# MainBoard.net
KiCad netlist of a schematic drawn in EAGLE
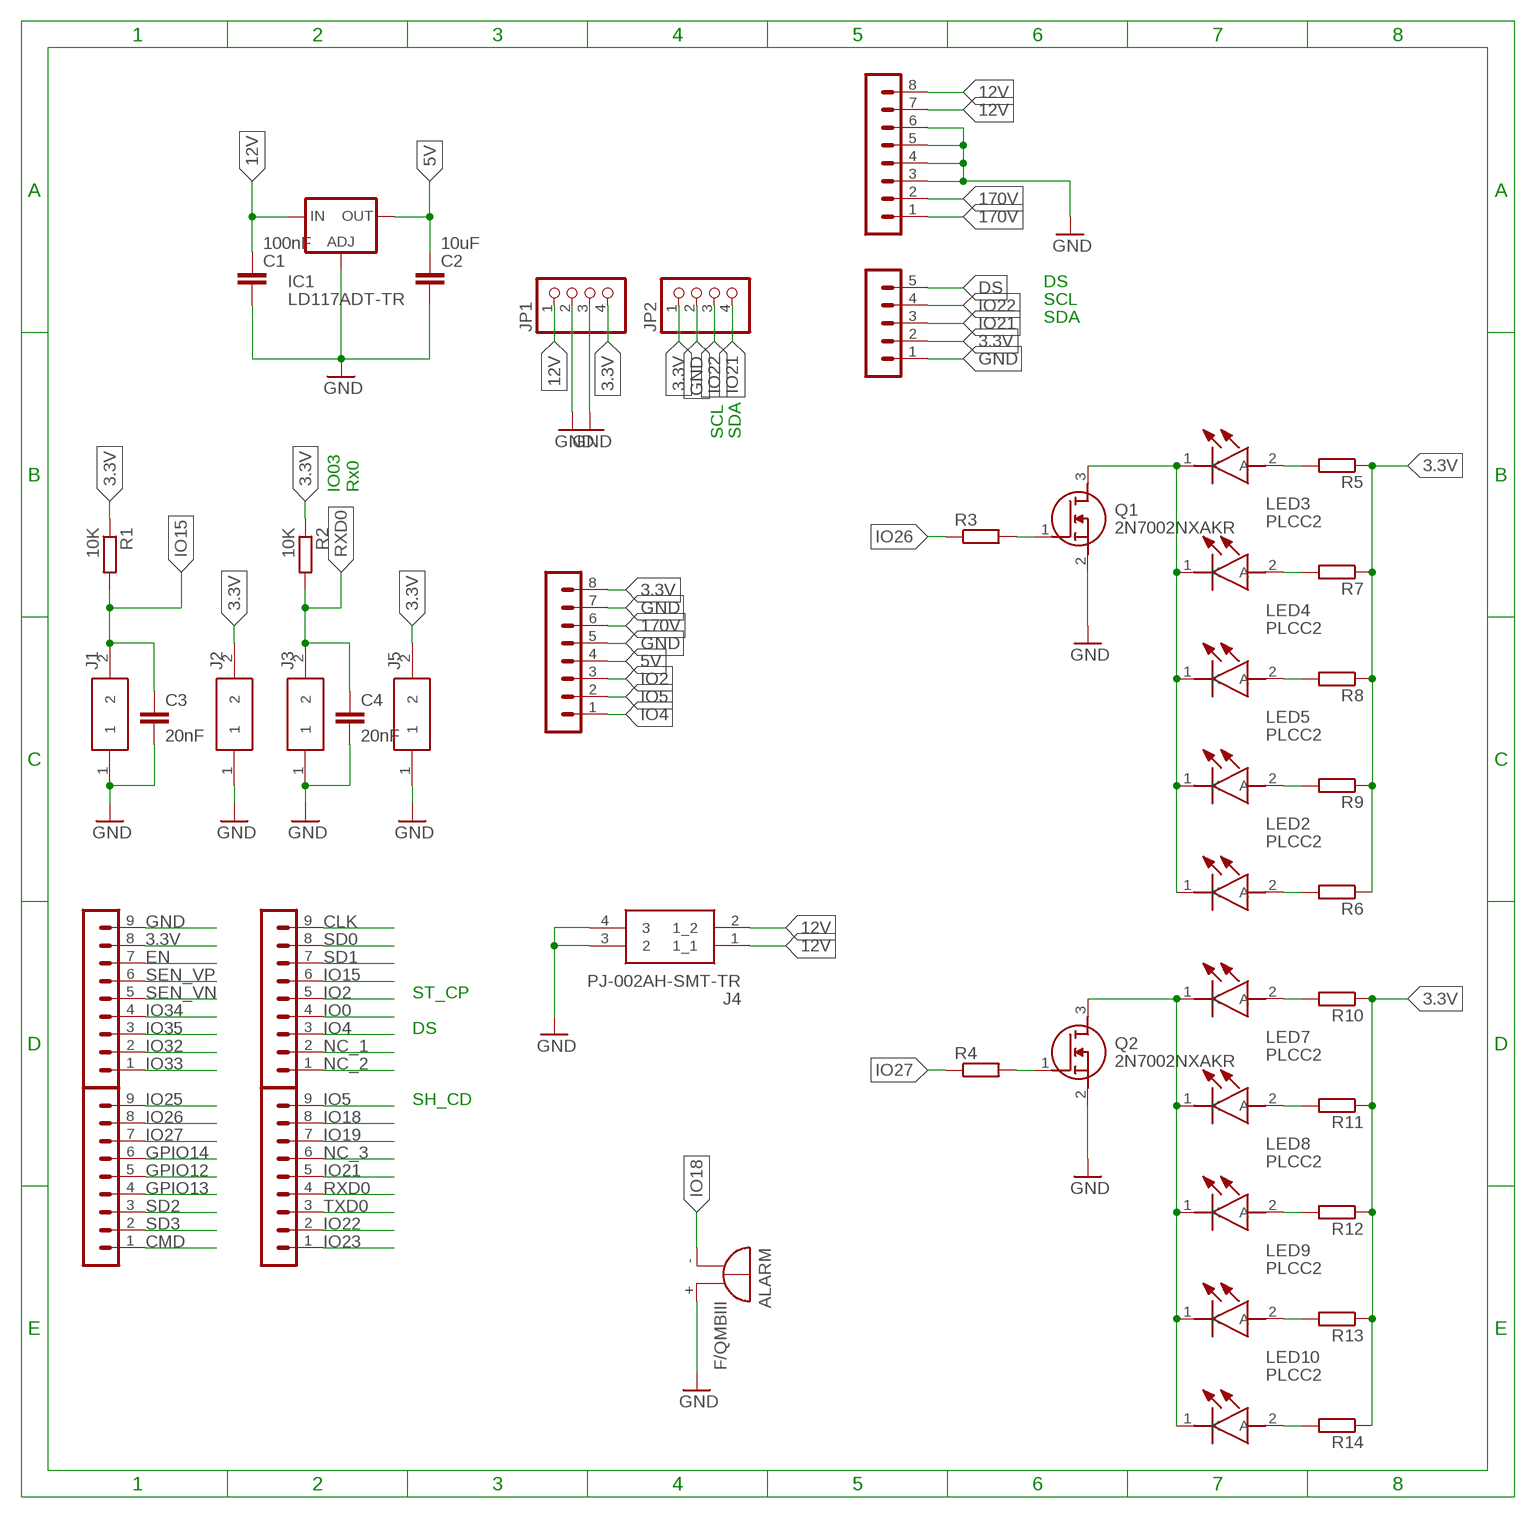
[diagram p0: schematic, sheet 1]

(export (version "E")
  (design (tool "Eeschema 10.0.6"))
  (components
    (comp (ref "ALARM")
      (value "F/QMBIII")
      (footprint "eagle-import:F_QMBIII")
      (libsource (lib "eagle-import") (part "F/QMBIII"))
    )
    (comp (ref "C1")
      (value "100nF")
      (footprint "eagle-import:C1206")
      (libsource (lib "eagle-import") (part "C-EU_1206C1206"))
    )
    (comp (ref "C2")
      (value "10uF")
      (footprint "eagle-import:C1206")
      (libsource (lib "eagle-import") (part "C-EU_1206C1206"))
    )
    (comp (ref "C3")
      (value "20nF")
      (footprint "eagle-import:C0805")
      (libsource (lib "eagle-import") (part "C-EU_805C0805"))
    )
    (comp (ref "C4")
      (value "20nF")
      (footprint "eagle-import:C0805")
      (libsource (lib "eagle-import") (part "C-EU_805C0805"))
    )
    (comp (ref "IC1")
      (value "LD117ADT-TR")
      (footprint "eagle-import:DPACK")
      (libsource (lib "eagle-import") (part "LD117A?DT-TR"))
    )
    (comp (ref "J1")
      (value "S2B-NSHSS-TB")
      (footprint "eagle-import:SM02B-NSHSS-TB")
      (fields (field (name "MANUFACTURER_PART_NUMBER") "SM02B-NSHSS-TB(LF)(SN)"))
      (libsource (lib "eagle-import") (part "S2B-NSHSS-TB"))
    )
    (comp (ref "J2")
      (value "S2B-NSHSS-TB")
      (footprint "eagle-import:SM02B-NSHSS-TB")
      (fields (field (name "MANUFACTURER_PART_NUMBER") "SM02B-NSHSS-TB(LF)(SN)"))
      (libsource (lib "eagle-import") (part "S2B-NSHSS-TB"))
    )
    (comp (ref "J3")
      (value "S2B-NSHSS-TB")
      (footprint "eagle-import:SM02B-NSHSS-TB")
      (fields (field (name "MANUFACTURER_PART_NUMBER") "SM02B-NSHSS-TB(LF)(SN)"))
      (libsource (lib "eagle-import") (part "S2B-NSHSS-TB"))
    )
    (comp (ref "J4")
      (value "PJ-002AH-SMT-TR")
      (footprint "eagle-import:PJ-002AH-SMT-TR")
      (fields (field (name "MOUSER_PART_NUMBER") "490-PJ-002AH-SMT-TR"))
      (libsource (lib "eagle-import") (part "PJ-002AH-SMT-TR"))
    )
    (comp (ref "J5")
      (value "S2B-NSHSS-TB")
      (footprint "eagle-import:SM02B-NSHSS-TB")
      (fields (field (name "MANUFACTURER_PART_NUMBER") "SM02B-NSHSS-TB(LF)(SN)"))
      (libsource (lib "eagle-import") (part "S2B-NSHSS-TB"))
    )
    (comp (ref "JP1")
      (value "PINHD-1X4")
      (footprint "eagle-import:1X04")
      (libsource (lib "eagle-import") (part "PINHD-1X4"))
    )
    (comp (ref "JP2")
      (value "PINHD-1X4")
      (footprint "eagle-import:1X04")
      (libsource (lib "eagle-import") (part "PINHD-1X4"))
    )
    (comp (ref "LED1")
      (value "PLCC2")
      (footprint "eagle-import:LEDM3528X200N")
      (fields
        (field (name "MANUFACTURER_PART_NUMBER") "ASMT-UWB1-NX302")
        (field (name "MOUSER2_PART_NUMBER") "630-ASMT-UWB1-NX302")
      )
      (libsource (lib "eagle-import") (part "PLCC2"))
    )
    (comp (ref "LED2")
      (value "PLCC2")
      (footprint "eagle-import:LEDM3528X200N")
      (fields
        (field (name "MANUFACTURER_PART_NUMBER") "ASMT-UWB1-NX302")
        (field (name "MOUSER2_PART_NUMBER") "630-ASMT-UWB1-NX302")
      )
      (libsource (lib "eagle-import") (part "PLCC2"))
    )
    (comp (ref "LED3")
      (value "PLCC2")
      (footprint "eagle-import:LEDM3528X200N")
      (fields
        (field (name "MANUFACTURER_PART_NUMBER") "ASMT-UWB1-NX302")
        (field (name "MOUSER2_PART_NUMBER") "630-ASMT-UWB1-NX302")
      )
      (libsource (lib "eagle-import") (part "PLCC2"))
    )
    (comp (ref "LED4")
      (value "PLCC2")
      (footprint "eagle-import:LEDM3528X200N")
      (fields
        (field (name "MANUFACTURER_PART_NUMBER") "ASMT-UWB1-NX302")
        (field (name "MOUSER2_PART_NUMBER") "630-ASMT-UWB1-NX302")
      )
      (libsource (lib "eagle-import") (part "PLCC2"))
    )
    (comp (ref "LED5")
      (value "PLCC2")
      (footprint "eagle-import:LEDM3528X200N")
      (fields
        (field (name "MANUFACTURER_PART_NUMBER") "ASMT-UWB1-NX302")
        (field (name "MOUSER2_PART_NUMBER") "630-ASMT-UWB1-NX302")
      )
      (libsource (lib "eagle-import") (part "PLCC2"))
    )
    (comp (ref "LED6")
      (value "PLCC2")
      (footprint "eagle-import:LEDM3528X200N")
      (fields
        (field (name "MANUFACTURER_PART_NUMBER") "ASMT-UWB1-NX302")
        (field (name "MOUSER2_PART_NUMBER") "630-ASMT-UWB1-NX302")
      )
      (libsource (lib "eagle-import") (part "PLCC2"))
    )
    (comp (ref "LED7")
      (value "PLCC2")
      (footprint "eagle-import:LEDM3528X200N")
      (fields
        (field (name "MANUFACTURER_PART_NUMBER") "ASMT-UWB1-NX302")
        (field (name "MOUSER2_PART_NUMBER") "630-ASMT-UWB1-NX302")
      )
      (libsource (lib "eagle-import") (part "PLCC2"))
    )
    (comp (ref "LED8")
      (value "PLCC2")
      (footprint "eagle-import:LEDM3528X200N")
      (fields
        (field (name "MANUFACTURER_PART_NUMBER") "ASMT-UWB1-NX302")
        (field (name "MOUSER2_PART_NUMBER") "630-ASMT-UWB1-NX302")
      )
      (libsource (lib "eagle-import") (part "PLCC2"))
    )
    (comp (ref "LED9")
      (value "PLCC2")
      (footprint "eagle-import:LEDM3528X200N")
      (fields
        (field (name "MANUFACTURER_PART_NUMBER") "ASMT-UWB1-NX302")
        (field (name "MOUSER2_PART_NUMBER") "630-ASMT-UWB1-NX302")
      )
      (libsource (lib "eagle-import") (part "PLCC2"))
    )
    (comp (ref "LED10")
      (value "PLCC2")
      (footprint "eagle-import:LEDM3528X200N")
      (fields
        (field (name "MANUFACTURER_PART_NUMBER") "ASMT-UWB1-NX302")
        (field (name "MOUSER2_PART_NUMBER") "630-ASMT-UWB1-NX302")
      )
      (libsource (lib "eagle-import") (part "PLCC2"))
    )
    (comp (ref "Q1")
      (value "2N7002NXAKR")
      (footprint "eagle-import:SOT95P230X110-3N")
      (fields (field (name "MOUSER_PART_NUMBER") "771-2N7002NXAKR"))
      (libsource (lib "eagle-import") (part "2N7002NXAKR"))
    )
    (comp (ref "Q2")
      (value "2N7002NXAKR")
      (footprint "eagle-import:SOT95P230X110-3N")
      (fields (field (name "MOUSER_PART_NUMBER") "771-2N7002NXAKR"))
      (libsource (lib "eagle-import") (part "2N7002NXAKR"))
    )
    (comp (ref "R1")
      (value "10K")
      (footprint "eagle-import:R1206")
      (libsource (lib "eagle-import") (part "R-EU_1206R1206"))
    )
    (comp (ref "R2")
      (value "10K")
      (footprint "eagle-import:R1206")
      (libsource (lib "eagle-import") (part "R-EU_1206R1206"))
    )
    (comp (ref "R3")
      (value "R-EU_1206R1206")
      (footprint "eagle-import:R1206")
      (libsource (lib "eagle-import") (part "R-EU_1206R1206"))
    )
    (comp (ref "R4")
      (value "R-EU_1206R1206")
      (footprint "eagle-import:R1206")
      (libsource (lib "eagle-import") (part "R-EU_1206R1206"))
    )
    (comp (ref "R5")
      (value "R-EU_1206R1206")
      (footprint "eagle-import:R1206")
      (libsource (lib "eagle-import") (part "R-EU_1206R1206"))
    )
    (comp (ref "R6")
      (value "R-EU_1206R1206")
      (footprint "eagle-import:R1206")
      (libsource (lib "eagle-import") (part "R-EU_1206R1206"))
    )
    (comp (ref "R7")
      (value "R-EU_1206R1206")
      (footprint "eagle-import:R1206")
      (libsource (lib "eagle-import") (part "R-EU_1206R1206"))
    )
    (comp (ref "R8")
      (value "R-EU_1206R1206")
      (footprint "eagle-import:R1206")
      (libsource (lib "eagle-import") (part "R-EU_1206R1206"))
    )
    (comp (ref "R9")
      (value "R-EU_1206R1206")
      (footprint "eagle-import:R1206")
      (libsource (lib "eagle-import") (part "R-EU_1206R1206"))
    )
    (comp (ref "R10")
      (value "R-EU_1206R1206")
      (footprint "eagle-import:R1206")
      (libsource (lib "eagle-import") (part "R-EU_1206R1206"))
    )
    (comp (ref "R11")
      (value "R-EU_1206R1206")
      (footprint "eagle-import:R1206")
      (libsource (lib "eagle-import") (part "R-EU_1206R1206"))
    )
    (comp (ref "R12")
      (value "R-EU_1206R1206")
      (footprint "eagle-import:R1206")
      (libsource (lib "eagle-import") (part "R-EU_1206R1206"))
    )
    (comp (ref "R13")
      (value "R-EU_1206R1206")
      (footprint "eagle-import:R1206")
      (libsource (lib "eagle-import") (part "R-EU_1206R1206"))
    )
    (comp (ref "R14")
      (value "R-EU_1206R1206")
      (footprint "eagle-import:R1206")
      (libsource (lib "eagle-import") (part "R-EU_1206R1206"))
    )
    (comp (ref "SV1")
      (value "PINHEADER-1X8")
      (footprint "eagle-import:MA08-1")
      (libsource (lib "eagle-import") (part "PINHEADER-1X8"))
    )
    (comp (ref "SV2")
      (value "PINHEADER-1X9")
      (footprint "eagle-import:MA09-1")
      (libsource (lib "eagle-import") (part "PINHEADER-1X9"))
    )
    (comp (ref "SV3")
      (value "PINHEADER-1X9")
      (footprint "eagle-import:MA09-1")
      (libsource (lib "eagle-import") (part "PINHEADER-1X9"))
    )
    (comp (ref "SV4")
      (value "PINHEADER-1X9")
      (footprint "eagle-import:MA09-1")
      (libsource (lib "eagle-import") (part "PINHEADER-1X9"))
    )
    (comp (ref "SV5")
      (value "PINHEADER-1X9")
      (footprint "eagle-import:MA09-1")
      (libsource (lib "eagle-import") (part "PINHEADER-1X9"))
    )
    (comp (ref "SV6")
      (value "MA05-1")
      (footprint "eagle-import:MA05-1")
      (libsource (lib "eagle-import") (part "MA05-1"))
    )
    (comp (ref "SV7")
      (value "PINHEADER-1X8")
      (footprint "eagle-import:MA08-1")
      (libsource (lib "eagle-import") (part "PINHEADER-1X8"))
    )
  )
  (nets
    (net (code "1") (name "/CLK") (class "Default")
      (node (ref "SV4") (pin "9") (pinfunction "9_9") (pintype "passive"))
    )
    (net (code "2") (name "/CMD") (class "Default")
      (node (ref "SV3") (pin "1") (pinfunction "1_1") (pintype "passive"))
    )
    (net (code "3") (name "/EN") (class "Default")
      (node (ref "SV2") (pin "7") (pinfunction "7_7") (pintype "passive"))
    )
    (net (code "4") (name "/GPIO12") (class "Default")
      (node (ref "SV3") (pin "5") (pinfunction "5_5") (pintype "passive"))
    )
    (net (code "5") (name "/GPIO13") (class "Default")
      (node (ref "SV3") (pin "4") (pinfunction "4_4") (pintype "passive"))
    )
    (net (code "6") (name "/GPIO14") (class "Default")
      (node (ref "SV3") (pin "6") (pinfunction "6_6") (pintype "passive"))
    )
    (net (code "7") (name "/IO0") (class "Default")
      (node (ref "SV4") (pin "4") (pinfunction "4_4") (pintype "passive"))
    )
    (net (code "8") (name "/IO19") (class "Default")
      (node (ref "SV5") (pin "7") (pinfunction "7_7") (pintype "passive"))
    )
    (net (code "9") (name "/IO23") (class "Default")
      (node (ref "SV5") (pin "1") (pinfunction "1_1") (pintype "passive"))
    )
    (net (code "10") (name "/IO25") (class "Default")
      (node (ref "SV3") (pin "9") (pinfunction "9_9") (pintype "passive"))
    )
    (net (code "11") (name "/IO32") (class "Default")
      (node (ref "SV2") (pin "2") (pinfunction "2_2") (pintype "passive"))
    )
    (net (code "12") (name "/IO33") (class "Default")
      (node (ref "SV2") (pin "1") (pinfunction "1_1") (pintype "passive"))
    )
    (net (code "13") (name "/IO34") (class "Default")
      (node (ref "SV2") (pin "4") (pinfunction "4_4") (pintype "passive"))
    )
    (net (code "14") (name "/IO35") (class "Default")
      (node (ref "SV2") (pin "3") (pinfunction "3_3") (pintype "passive"))
    )
    (net (code "15") (name "/NC_1") (class "Default")
      (node (ref "SV4") (pin "2") (pinfunction "2_2") (pintype "passive"))
    )
    (net (code "16") (name "/NC_2") (class "Default")
      (node (ref "SV4") (pin "1") (pinfunction "1_1") (pintype "passive"))
    )
    (net (code "17") (name "/NC_3") (class "Default")
      (node (ref "SV5") (pin "6") (pinfunction "6_6") (pintype "passive"))
    )
    (net (code "18") (name "/SD0") (class "Default")
      (node (ref "SV4") (pin "8") (pinfunction "8_8") (pintype "passive"))
    )
    (net (code "19") (name "/SD1") (class "Default")
      (node (ref "SV4") (pin "7") (pinfunction "7_7") (pintype "passive"))
    )
    (net (code "20") (name "/SD2") (class "Default")
      (node (ref "SV3") (pin "3") (pinfunction "3_3") (pintype "passive"))
    )
    (net (code "21") (name "/SD3") (class "Default")
      (node (ref "SV3") (pin "2") (pinfunction "2_2") (pintype "passive"))
    )
    (net (code "22") (name "/SEN_VN") (class "Default")
      (node (ref "SV2") (pin "5") (pinfunction "5_5") (pintype "passive"))
    )
    (net (code "23") (name "/SEN_VP") (class "Default")
      (node (ref "SV2") (pin "6") (pinfunction "6_6") (pintype "passive"))
    )
    (net (code "24") (name "/TXD0") (class "Default")
      (node (ref "SV5") (pin "3") (pinfunction "3_3") (pintype "passive"))
    )
    (net (code "25") (name "3.3V") (class "Default")
      (node (ref "J2") (pin "2") (pinfunction "2_2") (pintype "bidirectional"))
      (node (ref "J5") (pin "2") (pinfunction "2_2") (pintype "bidirectional"))
      (node (ref "JP1") (pin "4") (pinfunction "4_4") (pintype "passive"))
      (node (ref "JP2") (pin "1") (pinfunction "1_1") (pintype "passive"))
      (node (ref "R1") (pin "1") (pinfunction "1_1") (pintype "passive"))
      (node (ref "R10") (pin "1") (pinfunction "1_1") (pintype "passive"))
      (node (ref "R11") (pin "1") (pinfunction "1_1") (pintype "passive"))
      (node (ref "R12") (pin "1") (pinfunction "1_1") (pintype "passive"))
      (node (ref "R13") (pin "1") (pinfunction "1_1") (pintype "passive"))
      (node (ref "R14") (pin "1") (pinfunction "1_1") (pintype "passive"))
      (node (ref "R2") (pin "1") (pinfunction "1_1") (pintype "passive"))
      (node (ref "R5") (pin "1") (pinfunction "1_1") (pintype "passive"))
      (node (ref "R6") (pin "1") (pinfunction "1_1") (pintype "passive"))
      (node (ref "R7") (pin "1") (pinfunction "1_1") (pintype "passive"))
      (node (ref "R8") (pin "1") (pinfunction "1_1") (pintype "passive"))
      (node (ref "R9") (pin "1") (pinfunction "1_1") (pintype "passive"))
      (node (ref "SV1") (pin "8") (pinfunction "8_8") (pintype "passive"))
      (node (ref "SV2") (pin "8") (pinfunction "8_8") (pintype "passive"))
      (node (ref "SV6") (pin "2") (pinfunction "2_2") (pintype "passive"))
    )
    (net (code "26") (name "5V") (class "Default")
      (node (ref "C2") (pin "1") (pinfunction "1_1") (pintype "passive"))
      (node (ref "IC1") (pin "4") (pinfunction "OUT_4") (pintype "passive"))
      (node (ref "SV1") (pin "4") (pinfunction "4_4") (pintype "passive"))
    )
    (net (code "27") (name "12V") (class "Default")
      (node (ref "C1") (pin "1") (pinfunction "1_1") (pintype "passive"))
      (node (ref "IC1") (pin "3") (pinfunction "IN_3") (pintype "input"))
      (node (ref "J4") (pin "1") (pinfunction "1_1_1") (pintype "bidirectional"))
      (node (ref "J4") (pin "2") (pinfunction "1_2_2") (pintype "bidirectional"))
      (node (ref "JP1") (pin "1") (pinfunction "1_1") (pintype "passive"))
      (node (ref "SV7") (pin "7") (pinfunction "7_7") (pintype "passive"))
      (node (ref "SV7") (pin "8") (pinfunction "8_8") (pintype "passive"))
    )
    (net (code "28") (name "170V") (class "Default")
      (node (ref "SV1") (pin "6") (pinfunction "6_6") (pintype "passive"))
      (node (ref "SV7") (pin "1") (pinfunction "1_1") (pintype "passive"))
      (node (ref "SV7") (pin "2") (pinfunction "2_2") (pintype "passive"))
    )
    (net (code "29") (name "DS") (class "Default")
      (node (ref "SV6") (pin "5") (pinfunction "5_5") (pintype "passive"))
    )
    (net (code "30") (name "GND") (class "Default")
      (node (ref "ALARM") (pin "+") (pinfunction "-_+") (pintype "passive"))
      (node (ref "C1") (pin "2") (pinfunction "2_2") (pintype "passive"))
      (node (ref "C2") (pin "2") (pinfunction "2_2") (pintype "passive"))
      (node (ref "C3") (pin "2") (pinfunction "2_2") (pintype "passive"))
      (node (ref "C4") (pin "2") (pinfunction "2_2") (pintype "passive"))
      (node (ref "IC1") (pin "1") (pinfunction "ADJ_1") (pintype "input"))
      (node (ref "J1") (pin "1") (pinfunction "1_1") (pintype "bidirectional"))
      (node (ref "J2") (pin "1") (pinfunction "1_1") (pintype "bidirectional"))
      (node (ref "J3") (pin "1") (pinfunction "1_1") (pintype "bidirectional"))
      (node (ref "J4") (pin "3") (pinfunction "2_3") (pintype "bidirectional"))
      (node (ref "J4") (pin "4") (pinfunction "3_4") (pintype "bidirectional"))
      (node (ref "J5") (pin "1") (pinfunction "1_1") (pintype "bidirectional"))
      (node (ref "JP1") (pin "2") (pinfunction "2_2") (pintype "passive"))
      (node (ref "JP1") (pin "3") (pinfunction "3_3") (pintype "passive"))
      (node (ref "JP2") (pin "2") (pinfunction "2_2") (pintype "passive"))
      (node (ref "Q1") (pin "2") (pinfunction "S_2") (pintype "bidirectional"))
      (node (ref "Q2") (pin "2") (pinfunction "S_2") (pintype "bidirectional"))
      (node (ref "SV1") (pin "5") (pinfunction "5_5") (pintype "passive"))
      (node (ref "SV1") (pin "7") (pinfunction "7_7") (pintype "passive"))
      (node (ref "SV2") (pin "9") (pinfunction "9_9") (pintype "passive"))
      (node (ref "SV6") (pin "1") (pinfunction "1_1") (pintype "passive"))
      (node (ref "SV7") (pin "3") (pinfunction "3_3") (pintype "passive"))
      (node (ref "SV7") (pin "4") (pinfunction "4_4") (pintype "passive"))
      (node (ref "SV7") (pin "5") (pinfunction "5_5") (pintype "passive"))
      (node (ref "SV7") (pin "6") (pinfunction "6_6") (pintype "passive"))
    )
    (net (code "31") (name "IO2") (class "Default")
      (node (ref "SV1") (pin "3") (pinfunction "3_3") (pintype "passive"))
      (node (ref "SV4") (pin "5") (pinfunction "5_5") (pintype "passive"))
    )
    (net (code "32") (name "IO4") (class "Default")
      (node (ref "SV1") (pin "1") (pinfunction "1_1") (pintype "passive"))
      (node (ref "SV4") (pin "3") (pinfunction "3_3") (pintype "passive"))
    )
    (net (code "33") (name "IO5") (class "Default")
      (node (ref "SV1") (pin "2") (pinfunction "2_2") (pintype "passive"))
      (node (ref "SV5") (pin "9") (pinfunction "9_9") (pintype "passive"))
    )
    (net (code "34") (name "IO15") (class "Default")
      (node (ref "C3") (pin "1") (pinfunction "1_1") (pintype "passive"))
      (node (ref "J1") (pin "2") (pinfunction "2_2") (pintype "bidirectional"))
      (node (ref "R1") (pin "2") (pinfunction "2_2") (pintype "passive"))
      (node (ref "SV4") (pin "6") (pinfunction "6_6") (pintype "passive"))
    )
    (net (code "35") (name "IO18") (class "Default")
      (node (ref "ALARM") (pin "-") (pinfunction "+_-") (pintype "passive"))
      (node (ref "SV5") (pin "8") (pinfunction "8_8") (pintype "passive"))
    )
    (net (code "36") (name "IO21") (class "Default")
      (node (ref "JP2") (pin "4") (pinfunction "4_4") (pintype "passive"))
      (node (ref "SV5") (pin "5") (pinfunction "5_5") (pintype "passive"))
      (node (ref "SV6") (pin "3") (pinfunction "3_3") (pintype "passive"))
    )
    (net (code "37") (name "IO22") (class "Default")
      (node (ref "JP2") (pin "3") (pinfunction "3_3") (pintype "passive"))
      (node (ref "SV5") (pin "2") (pinfunction "2_2") (pintype "passive"))
      (node (ref "SV6") (pin "4") (pinfunction "4_4") (pintype "passive"))
    )
    (net (code "38") (name "IO26") (class "Default")
      (node (ref "R3") (pin "1") (pinfunction "1_1") (pintype "passive"))
      (node (ref "SV3") (pin "8") (pinfunction "8_8") (pintype "passive"))
    )
    (net (code "39") (name "IO27") (class "Default")
      (node (ref "R4") (pin "1") (pinfunction "1_1") (pintype "passive"))
      (node (ref "SV3") (pin "7") (pinfunction "7_7") (pintype "passive"))
    )
    (net (code "40") (name "Net-(LED1-A)") (class "Default")
      (node (ref "LED1") (pin "2") (pinfunction "A_2") (pintype "bidirectional"))
      (node (ref "R5") (pin "2") (pinfunction "2_2") (pintype "passive"))
    )
    (net (code "41") (name "Net-(LED1-K)") (class "Default")
      (node (ref "LED1") (pin "1") (pinfunction "K_1") (pintype "bidirectional"))
      (node (ref "LED2") (pin "1") (pinfunction "K_1") (pintype "bidirectional"))
      (node (ref "LED3") (pin "1") (pinfunction "K_1") (pintype "bidirectional"))
      (node (ref "LED4") (pin "1") (pinfunction "K_1") (pintype "bidirectional"))
      (node (ref "LED5") (pin "1") (pinfunction "K_1") (pintype "bidirectional"))
      (node (ref "Q1") (pin "3") (pinfunction "D_3") (pintype "bidirectional"))
    )
    (net (code "42") (name "Net-(LED2-A)") (class "Default")
      (node (ref "LED2") (pin "2") (pinfunction "A_2") (pintype "bidirectional"))
      (node (ref "R6") (pin "2") (pinfunction "2_2") (pintype "passive"))
    )
    (net (code "43") (name "Net-(LED3-A)") (class "Default")
      (node (ref "LED3") (pin "2") (pinfunction "A_2") (pintype "bidirectional"))
      (node (ref "R7") (pin "2") (pinfunction "2_2") (pintype "passive"))
    )
    (net (code "44") (name "Net-(LED4-A)") (class "Default")
      (node (ref "LED4") (pin "2") (pinfunction "A_2") (pintype "bidirectional"))
      (node (ref "R8") (pin "2") (pinfunction "2_2") (pintype "passive"))
    )
    (net (code "45") (name "Net-(LED5-A)") (class "Default")
      (node (ref "LED5") (pin "2") (pinfunction "A_2") (pintype "bidirectional"))
      (node (ref "R9") (pin "2") (pinfunction "2_2") (pintype "passive"))
    )
    (net (code "46") (name "Net-(LED6-A)") (class "Default")
      (node (ref "LED6") (pin "2") (pinfunction "A_2") (pintype "bidirectional"))
      (node (ref "R10") (pin "2") (pinfunction "2_2") (pintype "passive"))
    )
    (net (code "47") (name "Net-(LED7-A)") (class "Default")
      (node (ref "LED7") (pin "2") (pinfunction "A_2") (pintype "bidirectional"))
      (node (ref "R11") (pin "2") (pinfunction "2_2") (pintype "passive"))
    )
    (net (code "48") (name "Net-(LED8-A)") (class "Default")
      (node (ref "LED8") (pin "2") (pinfunction "A_2") (pintype "bidirectional"))
      (node (ref "R12") (pin "2") (pinfunction "2_2") (pintype "passive"))
    )
    (net (code "49") (name "Net-(LED9-A)") (class "Default")
      (node (ref "LED9") (pin "2") (pinfunction "A_2") (pintype "bidirectional"))
      (node (ref "R13") (pin "2") (pinfunction "2_2") (pintype "passive"))
    )
    (net (code "50") (name "Net-(LED10-A)") (class "Default")
      (node (ref "LED10") (pin "2") (pinfunction "A_2") (pintype "bidirectional"))
      (node (ref "R14") (pin "2") (pinfunction "2_2") (pintype "passive"))
    )
    (net (code "51") (name "Net-(LED10-K)") (class "Default")
      (node (ref "LED10") (pin "1") (pinfunction "K_1") (pintype "bidirectional"))
      (node (ref "LED6") (pin "1") (pinfunction "K_1") (pintype "bidirectional"))
      (node (ref "LED7") (pin "1") (pinfunction "K_1") (pintype "bidirectional"))
      (node (ref "LED8") (pin "1") (pinfunction "K_1") (pintype "bidirectional"))
      (node (ref "LED9") (pin "1") (pinfunction "K_1") (pintype "bidirectional"))
      (node (ref "Q2") (pin "3") (pinfunction "D_3") (pintype "bidirectional"))
    )
    (net (code "52") (name "Net-(Q1-G)") (class "Default")
      (node (ref "Q1") (pin "1") (pinfunction "G_1") (pintype "bidirectional"))
      (node (ref "R3") (pin "2") (pinfunction "2_2") (pintype "passive"))
    )
    (net (code "53") (name "Net-(Q2-G)") (class "Default")
      (node (ref "Q2") (pin "1") (pinfunction "G_1") (pintype "bidirectional"))
      (node (ref "R4") (pin "2") (pinfunction "2_2") (pintype "passive"))
    )
    (net (code "54") (name "RXD0") (class "Default")
      (node (ref "C4") (pin "1") (pinfunction "1_1") (pintype "passive"))
      (node (ref "J3") (pin "2") (pinfunction "2_2") (pintype "bidirectional"))
      (node (ref "R2") (pin "2") (pinfunction "2_2") (pintype "passive"))
      (node (ref "SV5") (pin "4") (pinfunction "4_4") (pintype "passive"))
    )
  )
)
